# Sheet1.net
KiCad netlist of a schematic drawn in Altium Designer
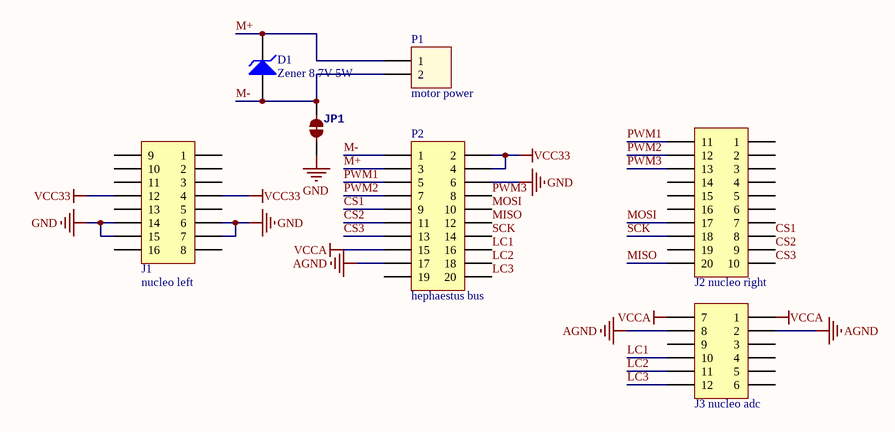
[diagram p0: Sheet1.SchDoc]

(export (version "E")
  (design (tool "Eeschema 10.0.6"))
  (components
    (comp (ref "D1")
      (value "Zener 8.7V 5W")
      (footprint "DIODE-0.7")
      (description "1N5345BRLG")
      (fields (field (name "PUBLISHER") "Altium Limited"))
      (libsource (lib "Miscellaneous Devices") (part "D Zener"))
    )
    (comp (ref "J1")
      (value "nucleo left")
      (footprint "61301621121")
      (description "WR-PHD 2.54 mm THT Dual Pin Header, 16p")
      (fields (field (name "PARTNUMBER") "61301621121") (field (name "PUBLISHER") "Wurth Elektronik"))
      (libsource (lib "ALTIUM-PHD_2_54_THT_PIN_HEADER_6130XX11121-rev16c") (part "61301621121"))
    )
    (comp (ref "J2")
      (value "nucleo right")
      (footprint "61302021121")
      (description "WR-PHD 2.54 mm THT Dual Pin Header, 20p")
      (fields (field (name "PARTNUMBER") "61302021121") (field (name "PUBLISHER") "Wurth Elektronik"))
      (libsource (lib "ALTIUM-PHD_2_54_THT_PIN_HEADER_6130XX11121-rev16c") (part "61302021121"))
    )
    (comp (ref "J3")
      (value "nucleo adc")
      (footprint "61301221121")
      (description "WR-PHD 2.54 mm THT Dual Pin Header, 12p")
      (fields (field (name "PARTNUMBER") "61301221121") (field (name "PUBLISHER") "Wurth Elektronik"))
      (libsource (lib "ALTIUM-PHD_2_54_THT_PIN_HEADER_6130XX11121-rev16c") (part "61301221121"))
    )
    (comp (ref "JP1")
      (value "JUMPER-PAD-2-NC_BY_TRACENO_SILK")
      (footprint "PAD-JUMPER-2-NC_BY_TRACE_NO_SILK")
      (libsource (lib "SparkFun-Passives") (part "JUMPER-PAD-2-NC_BY_TRACENO_SILK"))
    )
    (comp (ref "P1")
      (value "motor power")
      (footprint "691213710002")
      (description "WR-TBL Serie 213 - 5.00 mm Horizontal Entry Modular, 2p")
      (fields (field (name "PART NUMBER") "691213710002") (field (name "PUBLISHER") "Wurth Elektronik"))
      (libsource (lib "ALTIUM-TBL_5_00_2537_HORIZONTAL_ENTRY_W_RISING_CAGE_69125371000x-rev17a") (part "691213710002"))
    )
    (comp (ref "P2")
      (value "hephaestus bus")
      (footprint "612020235121")
      (description "WR-BHD 2.54mm Male Box Header High Temperature")
      (fields
        (field (name "MANUFACTURER") "Wurth Elektronik")
        (field (name "PARTNO") "612020235121")
        (field (name "CREATED BY") "Baojun Chen")
      )
      (libsource (lib "ALTIUM-BHD_2_54_MALE_BOX_HEADER_6120XX21621-rev16b") (part "612020235121"))
    )
  )
  (nets
    (net (code "1") (name "/CS1") (class "Default")
      (node (ref "J2") (pin "8") (pinfunction "8_8") (pintype "passive"))
      (node (ref "P2") (pin "9") (pinfunction "9_9") (pintype "passive"))
    )
    (net (code "2") (name "/CS2") (class "Default")
      (node (ref "J2") (pin "9") (pinfunction "9_9") (pintype "passive"))
      (node (ref "P2") (pin "11") (pinfunction "11_11") (pintype "passive"))
    )
    (net (code "3") (name "/CS3") (class "Default")
      (node (ref "J2") (pin "10") (pinfunction "10_10") (pintype "passive"))
      (node (ref "P2") (pin "13") (pinfunction "13_13") (pintype "passive"))
    )
    (net (code "4") (name "/LC1") (class "Default")
      (node (ref "J3") (pin "10") (pinfunction "10_10") (pintype "passive"))
      (node (ref "P2") (pin "16") (pinfunction "16_16") (pintype "passive"))
    )
    (net (code "5") (name "/LC2") (class "Default")
      (node (ref "J3") (pin "11") (pinfunction "11_11") (pintype "passive"))
      (node (ref "P2") (pin "18") (pinfunction "18_18") (pintype "passive"))
    )
    (net (code "6") (name "/LC3") (class "Default")
      (node (ref "J3") (pin "12") (pinfunction "12_12") (pintype "passive"))
      (node (ref "P2") (pin "20") (pinfunction "20_20") (pintype "passive"))
    )
    (net (code "7") (name "/M+") (class "Default")
      (node (ref "D1") (pin "2") (pinfunction "K_2") (pintype "passive"))
      (node (ref "P1") (pin "1") (pinfunction "1_1") (pintype "passive"))
      (node (ref "P2") (pin "3") (pinfunction "3_3") (pintype "passive"))
    )
    (net (code "8") (name "/M-") (class "Default")
      (node (ref "D1") (pin "1") (pinfunction "A_1") (pintype "passive"))
      (node (ref "JP1") (pin "2") (pinfunction "2_2") (pintype "passive"))
      (node (ref "P1") (pin "2") (pinfunction "2_2") (pintype "passive"))
      (node (ref "P2") (pin "1") (pinfunction "1_1") (pintype "passive"))
    )
    (net (code "9") (name "/MISO") (class "Default")
      (node (ref "J2") (pin "20") (pinfunction "20_20") (pintype "passive"))
      (node (ref "P2") (pin "12") (pinfunction "12_12") (pintype "passive"))
    )
    (net (code "10") (name "/MOSI") (class "Default")
      (node (ref "J2") (pin "17") (pinfunction "17_17") (pintype "passive"))
      (node (ref "P2") (pin "10") (pinfunction "10_10") (pintype "passive"))
    )
    (net (code "11") (name "/PWM1") (class "Default")
      (node (ref "J2") (pin "11") (pinfunction "11_11") (pintype "passive"))
      (node (ref "P2") (pin "5") (pinfunction "5_5") (pintype "passive"))
    )
    (net (code "12") (name "/PWM2") (class "Default")
      (node (ref "J2") (pin "12") (pinfunction "12_12") (pintype "passive"))
      (node (ref "P2") (pin "7") (pinfunction "7_7") (pintype "passive"))
    )
    (net (code "13") (name "/PWM3") (class "Default")
      (node (ref "J2") (pin "13") (pinfunction "13_13") (pintype "passive"))
      (node (ref "P2") (pin "8") (pinfunction "8_8") (pintype "passive"))
    )
    (net (code "14") (name "/SCK") (class "Default")
      (node (ref "J2") (pin "18") (pinfunction "18_18") (pintype "passive"))
      (node (ref "P2") (pin "14") (pinfunction "14_14") (pintype "passive"))
    )
    (net (code "15") (name "AGND") (class "Default")
      (node (ref "J3") (pin "2") (pinfunction "2_2") (pintype "passive"))
      (node (ref "J3") (pin "8") (pinfunction "8_8") (pintype "passive"))
      (node (ref "P2") (pin "17") (pinfunction "17_17") (pintype "passive"))
    )
    (net (code "16") (name "GND") (class "Default")
      (node (ref "J1") (pin "14") (pinfunction "14_14") (pintype "passive"))
      (node (ref "J1") (pin "15") (pinfunction "15_15") (pintype "passive"))
      (node (ref "J1") (pin "6") (pinfunction "6_6") (pintype "passive"))
      (node (ref "J1") (pin "7") (pinfunction "7_7") (pintype "passive"))
      (node (ref "JP1") (pin "1") (pinfunction "1_1") (pintype "passive"))
      (node (ref "P2") (pin "6") (pinfunction "6_6") (pintype "passive"))
    )
    (net (code "17") (name "VCC33") (class "Default")
      (node (ref "J1") (pin "12") (pinfunction "12_12") (pintype "passive"))
      (node (ref "J1") (pin "4") (pinfunction "4_4") (pintype "passive"))
      (node (ref "P2") (pin "2") (pinfunction "2_2") (pintype "passive"))
      (node (ref "P2") (pin "4") (pinfunction "4_4") (pintype "passive"))
    )
    (net (code "18") (name "VCCA") (class "Default")
      (node (ref "J3") (pin "1") (pinfunction "1_1") (pintype "passive"))
      (node (ref "J3") (pin "7") (pinfunction "7_7") (pintype "passive"))
      (node (ref "P2") (pin "15") (pinfunction "15_15") (pintype "passive"))
    )
    (net (code "19") (name "unconnected-(J1-Pad1)") (class "Default")
      (node (ref "J1") (pin "1") (pinfunction "1_1") (pintype "passive"))
    )
    (net (code "20") (name "unconnected-(J1-Pad2)") (class "Default")
      (node (ref "J1") (pin "2") (pinfunction "2_2") (pintype "passive"))
    )
    (net (code "21") (name "unconnected-(J1-Pad3)") (class "Default")
      (node (ref "J1") (pin "3") (pinfunction "3_3") (pintype "passive"))
    )
    (net (code "22") (name "unconnected-(J1-Pad5)") (class "Default")
      (node (ref "J1") (pin "5") (pinfunction "5_5") (pintype "passive"))
    )
    (net (code "23") (name "unconnected-(J1-Pad8)") (class "Default")
      (node (ref "J1") (pin "8") (pinfunction "8_8") (pintype "passive"))
    )
    (net (code "24") (name "unconnected-(J1-Pad9)") (class "Default")
      (node (ref "J1") (pin "9") (pinfunction "9_9") (pintype "passive"))
    )
    (net (code "25") (name "unconnected-(J1-Pad10)") (class "Default")
      (node (ref "J1") (pin "10") (pinfunction "10_10") (pintype "passive"))
    )
    (net (code "26") (name "unconnected-(J1-Pad11)") (class "Default")
      (node (ref "J1") (pin "11") (pinfunction "11_11") (pintype "passive"))
    )
    (net (code "27") (name "unconnected-(J1-Pad13)") (class "Default")
      (node (ref "J1") (pin "13") (pinfunction "13_13") (pintype "passive"))
    )
    (net (code "28") (name "unconnected-(J1-Pad16)") (class "Default")
      (node (ref "J1") (pin "16") (pinfunction "16_16") (pintype "passive"))
    )
    (net (code "29") (name "unconnected-(J2-Pad1)") (class "Default")
      (node (ref "J2") (pin "1") (pinfunction "1_1") (pintype "passive"))
    )
    (net (code "30") (name "unconnected-(J2-Pad2)") (class "Default")
      (node (ref "J2") (pin "2") (pinfunction "2_2") (pintype "passive"))
    )
    (net (code "31") (name "unconnected-(J2-Pad3)") (class "Default")
      (node (ref "J2") (pin "3") (pinfunction "3_3") (pintype "passive"))
    )
    (net (code "32") (name "unconnected-(J2-Pad4)") (class "Default")
      (node (ref "J2") (pin "4") (pinfunction "4_4") (pintype "passive"))
    )
    (net (code "33") (name "unconnected-(J2-Pad5)") (class "Default")
      (node (ref "J2") (pin "5") (pinfunction "5_5") (pintype "passive"))
    )
    (net (code "34") (name "unconnected-(J2-Pad6)") (class "Default")
      (node (ref "J2") (pin "6") (pinfunction "6_6") (pintype "passive"))
    )
    (net (code "35") (name "unconnected-(J2-Pad7)") (class "Default")
      (node (ref "J2") (pin "7") (pinfunction "7_7") (pintype "passive"))
    )
    (net (code "36") (name "unconnected-(J2-Pad14)") (class "Default")
      (node (ref "J2") (pin "14") (pinfunction "14_14") (pintype "passive"))
    )
    (net (code "37") (name "unconnected-(J2-Pad15)") (class "Default")
      (node (ref "J2") (pin "15") (pinfunction "15_15") (pintype "passive"))
    )
    (net (code "38") (name "unconnected-(J2-Pad16)") (class "Default")
      (node (ref "J2") (pin "16") (pinfunction "16_16") (pintype "passive"))
    )
    (net (code "39") (name "unconnected-(J2-Pad19)") (class "Default")
      (node (ref "J2") (pin "19") (pinfunction "19_19") (pintype "passive"))
    )
    (net (code "40") (name "unconnected-(J3-Pad3)") (class "Default")
      (node (ref "J3") (pin "3") (pinfunction "3_3") (pintype "passive"))
    )
    (net (code "41") (name "unconnected-(J3-Pad4)") (class "Default")
      (node (ref "J3") (pin "4") (pinfunction "4_4") (pintype "passive"))
    )
    (net (code "42") (name "unconnected-(J3-Pad5)") (class "Default")
      (node (ref "J3") (pin "5") (pinfunction "5_5") (pintype "passive"))
    )
    (net (code "43") (name "unconnected-(J3-Pad6)") (class "Default")
      (node (ref "J3") (pin "6") (pinfunction "6_6") (pintype "passive"))
    )
    (net (code "44") (name "unconnected-(J3-Pad9)") (class "Default")
      (node (ref "J3") (pin "9") (pinfunction "9_9") (pintype "passive"))
    )
    (net (code "45") (name "unconnected-(P2-Pad19)") (class "Default")
      (node (ref "P2") (pin "19") (pinfunction "19_19") (pintype "passive"))
    )
  )
)
